# htr_reg.net
KiCad netlist of a schematic drawn in EAGLE
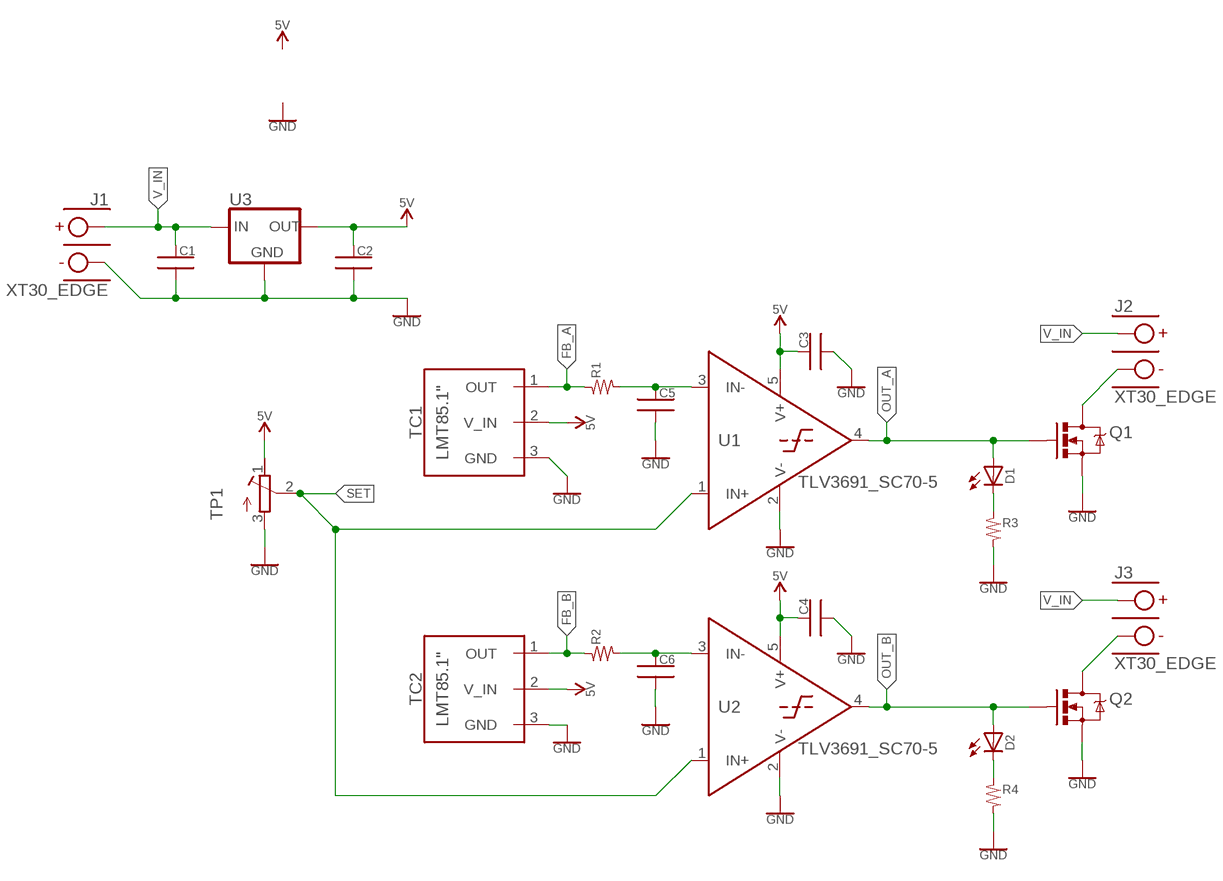
[diagram p0: schematic, sheet 1]

(export (version "E")
  (design (tool "Eeschema 10.0.6"))
  (components
    (comp (ref "C1")
      (value "CAP_SMD_0603")
      (footprint "eagle-import:0603")
      (libsource (lib "eagle-import") (part "CAP_SMD_0603"))
    )
    (comp (ref "C2")
      (value "CAP_SMD_0603")
      (footprint "eagle-import:0603")
      (libsource (lib "eagle-import") (part "CAP_SMD_0603"))
    )
    (comp (ref "C3")
      (value "CAP_SMD_0603")
      (footprint "eagle-import:0603")
      (libsource (lib "eagle-import") (part "CAP_SMD_0603"))
    )
    (comp (ref "C4")
      (value "CAP_SMD_0603")
      (footprint "eagle-import:0603")
      (libsource (lib "eagle-import") (part "CAP_SMD_0603"))
    )
    (comp (ref "C5")
      (value "CAP_SMD_0603")
      (footprint "eagle-import:0603")
      (libsource (lib "eagle-import") (part "CAP_SMD_0603"))
    )
    (comp (ref "C6")
      (value "CAP_SMD_0603")
      (footprint "eagle-import:0603")
      (libsource (lib "eagle-import") (part "CAP_SMD_0603"))
    )
    (comp (ref "D1")
      (value "LED0603")
      (footprint "eagle-import:LED-0603")
      (libsource (lib "eagle-import") (part "LED0603"))
    )
    (comp (ref "D2")
      (value "LED0603")
      (footprint "eagle-import:LED-0603")
      (libsource (lib "eagle-import") (part "LED0603"))
    )
    (comp (ref "J1")
      (value "XT30_EDGE")
      (footprint "eagle-import:XT30_EDGEMOUNT")
      (libsource (lib "eagle-import") (part "XT30_EDGE"))
    )
    (comp (ref "J2")
      (value "XT30_EDGE")
      (footprint "eagle-import:XT30_EDGEMOUNT")
      (libsource (lib "eagle-import") (part "XT30_EDGE"))
    )
    (comp (ref "J3")
      (value "XT30_EDGE")
      (footprint "eagle-import:XT30_EDGEMOUNT")
      (libsource (lib "eagle-import") (part "XT30_EDGE"))
    )
    (comp (ref "Q1")
      (value "MOSFET_N-CHANNEL_SOT23-3")
      (footprint "eagle-import:SOT23-3")
      (libsource (lib "eagle-import") (part "MOSFET_N-CHANNEL_SOT23-3"))
    )
    (comp (ref "Q2")
      (value "MOSFET_N-CHANNEL_SOT23-3")
      (footprint "eagle-import:SOT23-3")
      (libsource (lib "eagle-import") (part "MOSFET_N-CHANNEL_SOT23-3"))
    )
    (comp (ref "R1")
      (value "RES_SMD0603")
      (footprint "eagle-import:0603")
      (libsource (lib "eagle-import") (part "RES_SMD0603"))
    )
    (comp (ref "R2")
      (value "RES_SMD0603")
      (footprint "eagle-import:0603")
      (libsource (lib "eagle-import") (part "RES_SMD0603"))
    )
    (comp (ref "R3")
      (value "RES_SMD0603")
      (footprint "eagle-import:0603")
      (libsource (lib "eagle-import") (part "RES_SMD0603"))
    )
    (comp (ref "R4")
      (value "RES_SMD0603")
      (footprint "eagle-import:0603")
      (libsource (lib "eagle-import") (part "RES_SMD0603"))
    )
    (comp (ref "TC1")
      (value "LMT85.1\"")
      (footprint "eagle-import:1X03")
      (libsource (lib "eagle-import") (part "LMT85.1{dblquote}"))
    )
    (comp (ref "TC2")
      (value "LMT85.1\"")
      (footprint "eagle-import:1X03")
      (libsource (lib "eagle-import") (part "LMT85.1{dblquote}"))
    )
    (comp (ref "TP1")
      (value "3296W")
      (footprint "eagle-import:3296W")
      (libsource (lib "eagle-import") (part "3296W"))
    )
    (comp (ref "U1")
      (value "TLV3691_SC70-5")
      (footprint "eagle-import:SC70-5")
      (libsource (lib "eagle-import") (part "TLV3691_SC70-5"))
    )
    (comp (ref "U2")
      (value "TLV3691_SC70-5")
      (footprint "eagle-import:SC70-5")
      (libsource (lib "eagle-import") (part "TLV3691_SC70-5"))
    )
    (comp (ref "U3")
      (value "78XX_VREG_B")
      (footprint "eagle-import:SOT23-3")
      (libsource (lib "eagle-import") (part "78XX_VREG_B"))
    )
  )
  (nets
    (net (code "1") (name "5V") (class "Default")
      (node (ref "C2") (pin "1") (pinfunction "1_1") (pintype "passive"))
      (node (ref "C3") (pin "1") (pinfunction "1_1") (pintype "passive"))
      (node (ref "C4") (pin "1") (pinfunction "1_1") (pintype "passive"))
      (node (ref "TC1") (pin "2") (pinfunction "V_IN_2") (pintype "bidirectional"))
      (node (ref "TC2") (pin "2") (pinfunction "V_IN_2") (pintype "bidirectional"))
      (node (ref "TP1") (pin "1") (pinfunction "E_1") (pintype "passive"))
      (node (ref "U1") (pin "5") (pinfunction "V+_5") (pintype "bidirectional"))
      (node (ref "U2") (pin "5") (pinfunction "V+_5") (pintype "bidirectional"))
      (node (ref "U3") (pin "2") (pinfunction "OUT_2") (pintype "passive"))
    )
    (net (code "2") (name "FB_A") (class "Default")
      (node (ref "R1") (pin "1") (pinfunction "1_1") (pintype "passive"))
      (node (ref "TC1") (pin "1") (pinfunction "OUT_1") (pintype "bidirectional"))
    )
    (net (code "3") (name "FB_B") (class "Default")
      (node (ref "R2") (pin "1") (pinfunction "1_1") (pintype "passive"))
      (node (ref "TC2") (pin "1") (pinfunction "OUT_1") (pintype "bidirectional"))
    )
    (net (code "4") (name "GND") (class "Default")
      (node (ref "C1") (pin "2") (pinfunction "2_2") (pintype "passive"))
      (node (ref "C2") (pin "2") (pinfunction "2_2") (pintype "passive"))
      (node (ref "C3") (pin "2") (pinfunction "2_2") (pintype "passive"))
      (node (ref "C4") (pin "2") (pinfunction "2_2") (pintype "passive"))
      (node (ref "C5") (pin "2") (pinfunction "2_2") (pintype "passive"))
      (node (ref "C6") (pin "2") (pinfunction "2_2") (pintype "passive"))
      (node (ref "J1") (pin "NEG") (pinfunction "NEG_NEG") (pintype "bidirectional"))
      (node (ref "Q1") (pin "2") (pinfunction "S_2") (pintype "passive"))
      (node (ref "Q2") (pin "2") (pinfunction "S_2") (pintype "passive"))
      (node (ref "R3") (pin "2") (pinfunction "2_2") (pintype "passive"))
      (node (ref "R4") (pin "2") (pinfunction "2_2") (pintype "passive"))
      (node (ref "TC1") (pin "3") (pinfunction "GND_3") (pintype "bidirectional"))
      (node (ref "TC2") (pin "3") (pinfunction "GND_3") (pintype "bidirectional"))
      (node (ref "TP1") (pin "3") (pinfunction "A_3") (pintype "passive"))
      (node (ref "U1") (pin "2") (pinfunction "V-_2") (pintype "bidirectional"))
      (node (ref "U2") (pin "2") (pinfunction "V-_2") (pintype "bidirectional"))
      (node (ref "U3") (pin "1") (pinfunction "GND_1") (pintype "input"))
    )
    (net (code "5") (name "Net-(D1-PadC)") (class "Default")
      (node (ref "D1") (pin "C") (pinfunction "C_C") (pintype "passive"))
      (node (ref "R3") (pin "1") (pinfunction "1_1") (pintype "passive"))
    )
    (net (code "6") (name "Net-(D2-PadC)") (class "Default")
      (node (ref "D2") (pin "C") (pinfunction "C_C") (pintype "passive"))
      (node (ref "R4") (pin "1") (pinfunction "1_1") (pintype "passive"))
    )
    (net (code "7") (name "Net-(Q1-D)") (class "Default")
      (node (ref "J2") (pin "NEG") (pinfunction "NEG_NEG") (pintype "bidirectional"))
      (node (ref "Q1") (pin "3") (pinfunction "D_3") (pintype "passive"))
    )
    (net (code "8") (name "Net-(Q2-D)") (class "Default")
      (node (ref "J3") (pin "NEG") (pinfunction "NEG_NEG") (pintype "bidirectional"))
      (node (ref "Q2") (pin "3") (pinfunction "D_3") (pintype "passive"))
    )
    (net (code "9") (name "Net-(U1-IN-)") (class "Default")
      (node (ref "C5") (pin "1") (pinfunction "1_1") (pintype "passive"))
      (node (ref "R1") (pin "2") (pinfunction "2_2") (pintype "passive"))
      (node (ref "U1") (pin "3") (pinfunction "IN-_3") (pintype "bidirectional"))
    )
    (net (code "10") (name "Net-(U2-IN-)") (class "Default")
      (node (ref "C6") (pin "1") (pinfunction "1_1") (pintype "passive"))
      (node (ref "R2") (pin "2") (pinfunction "2_2") (pintype "passive"))
      (node (ref "U2") (pin "3") (pinfunction "IN-_3") (pintype "bidirectional"))
    )
    (net (code "11") (name "OUT_A") (class "Default")
      (node (ref "D1") (pin "A") (pinfunction "A_A") (pintype "passive"))
      (node (ref "Q1") (pin "1") (pinfunction "G_1") (pintype "passive"))
      (node (ref "U1") (pin "4") (pinfunction "OUT_4") (pintype "bidirectional"))
    )
    (net (code "12") (name "OUT_B") (class "Default")
      (node (ref "D2") (pin "A") (pinfunction "A_A") (pintype "passive"))
      (node (ref "Q2") (pin "1") (pinfunction "G_1") (pintype "passive"))
      (node (ref "U2") (pin "4") (pinfunction "OUT_4") (pintype "bidirectional"))
    )
    (net (code "13") (name "SET") (class "Default")
      (node (ref "TP1") (pin "2") (pinfunction "S_2") (pintype "passive"))
      (node (ref "U1") (pin "1") (pinfunction "IN+_1") (pintype "bidirectional"))
      (node (ref "U2") (pin "1") (pinfunction "IN+_1") (pintype "bidirectional"))
    )
    (net (code "14") (name "V_IN") (class "Default")
      (node (ref "C1") (pin "1") (pinfunction "1_1") (pintype "passive"))
      (node (ref "J1") (pin "POS") (pinfunction "POS_POS") (pintype "bidirectional"))
      (node (ref "J2") (pin "POS") (pinfunction "POS_POS") (pintype "bidirectional"))
      (node (ref "J3") (pin "POS") (pinfunction "POS_POS") (pintype "bidirectional"))
      (node (ref "U3") (pin "3") (pinfunction "IN_3") (pintype "input"))
    )
  )
)
